# Gloves_Flex_PCB.net
KiCad netlist of a schematic drawn in EAGLE
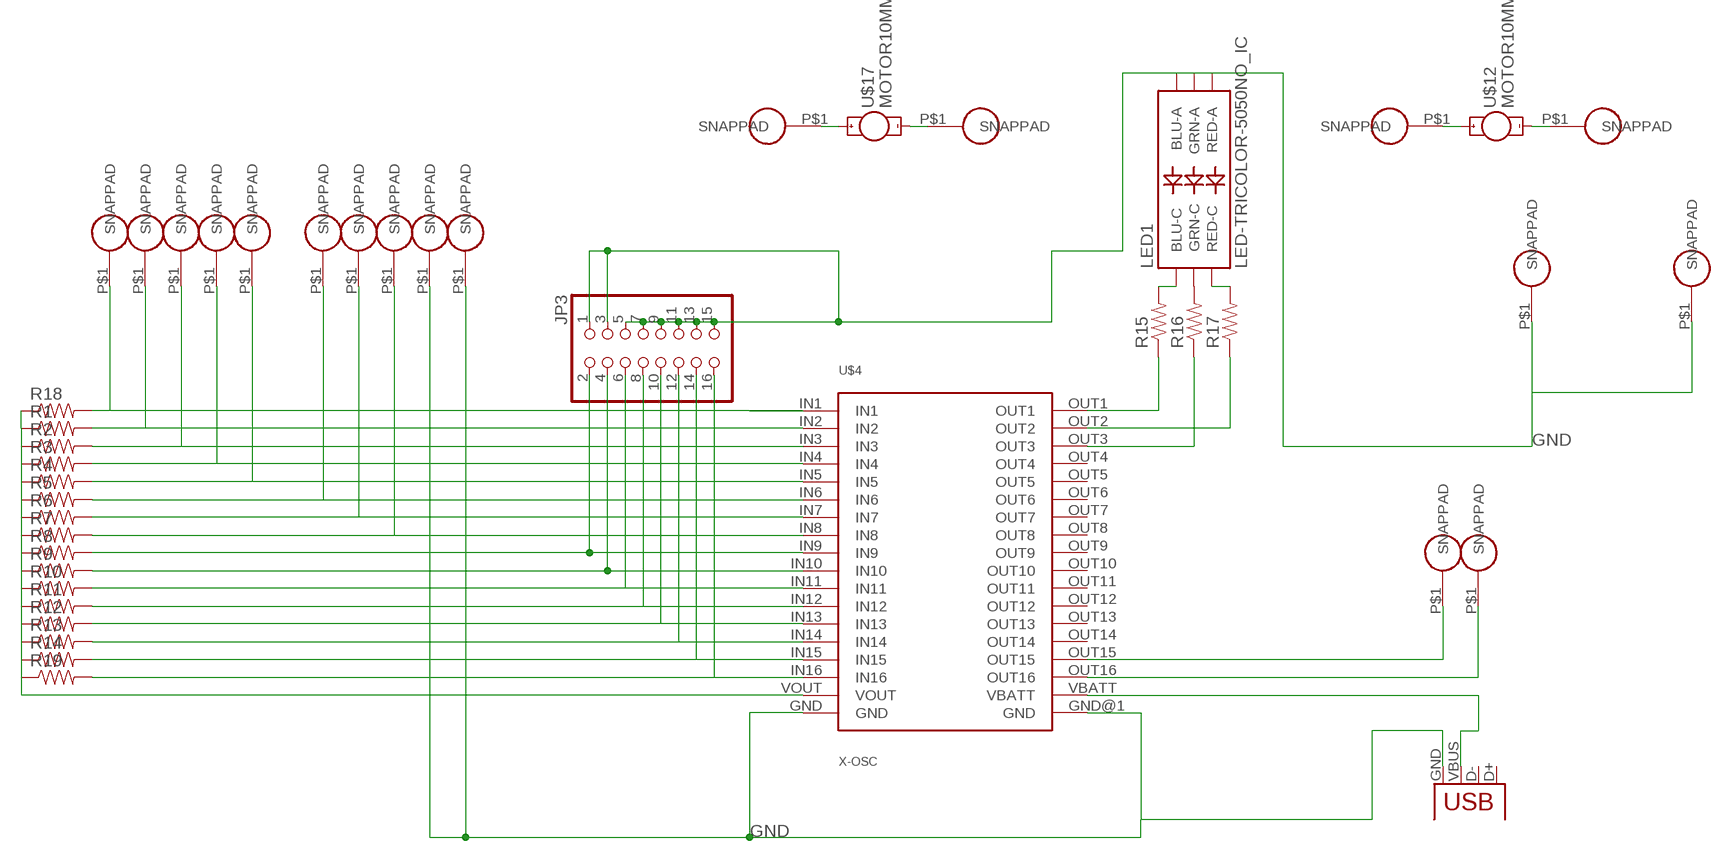
[diagram p0: schematic, sheet 1]

(export (version "E")
  (design (tool "Eeschema 10.0.6"))
  (components
    (comp (ref "JP3")
      (value "PINHD-2X8")
      (footprint "eagle-import:2X08")
      (libsource (lib "eagle-import") (part "PINHD-2X8"))
    )
    (comp (ref "LED1")
      (value "LED-TRICOLOR-5050NO_IC")
      (footprint "eagle-import:LED-TRICOLOR-5050")
      (libsource (lib "eagle-import") (part "LED-TRICOLOR-5050NO_IC"))
    )
    (comp (ref "R1")
      (value "RESISTOR0805-RES")
      (footprint "eagle-import:0805")
      (libsource (lib "eagle-import") (part "RESISTOR0805-RES"))
    )
    (comp (ref "R2")
      (value "RESISTOR0805-RES")
      (footprint "eagle-import:0805")
      (libsource (lib "eagle-import") (part "RESISTOR0805-RES"))
    )
    (comp (ref "R3")
      (value "RESISTOR0805-RES")
      (footprint "eagle-import:0805")
      (libsource (lib "eagle-import") (part "RESISTOR0805-RES"))
    )
    (comp (ref "R4")
      (value "RESISTOR0805-RES")
      (footprint "eagle-import:0805")
      (libsource (lib "eagle-import") (part "RESISTOR0805-RES"))
    )
    (comp (ref "R5")
      (value "RESISTOR0805-RES")
      (footprint "eagle-import:0805")
      (libsource (lib "eagle-import") (part "RESISTOR0805-RES"))
    )
    (comp (ref "R6")
      (value "RESISTOR0805-RES")
      (footprint "eagle-import:0805")
      (libsource (lib "eagle-import") (part "RESISTOR0805-RES"))
    )
    (comp (ref "R7")
      (value "RESISTOR0805-RES")
      (footprint "eagle-import:0805")
      (libsource (lib "eagle-import") (part "RESISTOR0805-RES"))
    )
    (comp (ref "R8")
      (value "RESISTOR0805-RES")
      (footprint "eagle-import:0805")
      (libsource (lib "eagle-import") (part "RESISTOR0805-RES"))
    )
    (comp (ref "R9")
      (value "RESISTOR0805-RES")
      (footprint "eagle-import:0805")
      (libsource (lib "eagle-import") (part "RESISTOR0805-RES"))
    )
    (comp (ref "R10")
      (value "RESISTOR0805-RES")
      (footprint "eagle-import:0805")
      (libsource (lib "eagle-import") (part "RESISTOR0805-RES"))
    )
    (comp (ref "R11")
      (value "RESISTOR0805-RES")
      (footprint "eagle-import:0805")
      (libsource (lib "eagle-import") (part "RESISTOR0805-RES"))
    )
    (comp (ref "R12")
      (value "RESISTOR0805-RES")
      (footprint "eagle-import:0805")
      (libsource (lib "eagle-import") (part "RESISTOR0805-RES"))
    )
    (comp (ref "R13")
      (value "RESISTOR0805-RES")
      (footprint "eagle-import:0805")
      (libsource (lib "eagle-import") (part "RESISTOR0805-RES"))
    )
    (comp (ref "R14")
      (value "RESISTOR0805-RES")
      (footprint "eagle-import:0805")
      (libsource (lib "eagle-import") (part "RESISTOR0805-RES"))
    )
    (comp (ref "R15")
      (value "RESISTOR0805-RES")
      (footprint "eagle-import:0805")
      (libsource (lib "eagle-import") (part "RESISTOR0805-RES"))
    )
    (comp (ref "R16")
      (value "RESISTOR0805-RES")
      (footprint "eagle-import:0805")
      (libsource (lib "eagle-import") (part "RESISTOR0805-RES"))
    )
    (comp (ref "R17")
      (value "RESISTOR0805-RES")
      (footprint "eagle-import:0805")
      (libsource (lib "eagle-import") (part "RESISTOR0805-RES"))
    )
    (comp (ref "R18")
      (value "RESISTOR0805-RES")
      (footprint "eagle-import:0805")
      (libsource (lib "eagle-import") (part "RESISTOR0805-RES"))
    )
    (comp (ref "R19")
      (value "RESISTOR0805-RES")
      (footprint "eagle-import:0805")
      (libsource (lib "eagle-import") (part "RESISTOR0805-RES"))
    )
    (comp (ref "U$1")
      (value "SNAP-PAD_7MM_ROUND")
      (footprint "eagle-import:SNAP-PAD_7MM_RD")
      (libsource (lib "eagle-import") (part "SNAP-PAD_7MM_ROUND"))
    )
    (comp (ref "U$2")
      (value "SNAP-PAD_7MM_ROUND")
      (footprint "eagle-import:SNAP-PAD_7MM_RD")
      (libsource (lib "eagle-import") (part "SNAP-PAD_7MM_ROUND"))
    )
    (comp (ref "U$3")
      (value "SNAP-PAD_7MM_ROUND")
      (footprint "eagle-import:SNAP-PAD_7MM_RD")
      (libsource (lib "eagle-import") (part "SNAP-PAD_7MM_ROUND"))
    )
    (comp (ref "U$4")
      (value "X-OSC")
      (footprint "eagle-import:X-OSC_SMD")
      (libsource (lib "eagle-import") (part "X-OSC"))
    )
    (comp (ref "U$6")
      (value "SNAP-PAD_7MM_ROUND")
      (footprint "eagle-import:SNAP-PAD_7MM_RD")
      (libsource (lib "eagle-import") (part "SNAP-PAD_7MM_ROUND"))
    )
    (comp (ref "U$7")
      (value "SNAP-PAD_7MM_ROUND")
      (footprint "eagle-import:SNAP-PAD_7MM_RD")
      (libsource (lib "eagle-import") (part "SNAP-PAD_7MM_ROUND"))
    )
    (comp (ref "U$8")
      (value "SNAP-PAD_7MM_ROUND")
      (footprint "eagle-import:SNAP-PAD_7MM_RD")
      (libsource (lib "eagle-import") (part "SNAP-PAD_7MM_ROUND"))
    )
    (comp (ref "U$9")
      (value "SNAP-PAD_7MM_ROUND")
      (footprint "eagle-import:SNAP-PAD_7MM_RD")
      (libsource (lib "eagle-import") (part "SNAP-PAD_7MM_ROUND"))
    )
    (comp (ref "U$10")
      (value "SNAP-PAD_7MM_ROUND")
      (footprint "eagle-import:SNAP-PAD_7MM_RD")
      (libsource (lib "eagle-import") (part "SNAP-PAD_7MM_ROUND"))
    )
    (comp (ref "U$11")
      (value "SNAP-PAD_7MM_ROUND")
      (footprint "eagle-import:SNAP-PAD_7MM_RD")
      (libsource (lib "eagle-import") (part "SNAP-PAD_7MM_ROUND"))
    )
    (comp (ref "U$12")
      (value "MOTOR10MM")
      (footprint "eagle-import:VIBE-MOTOR-10MM")
      (libsource (lib "eagle-import") (part "MOTOR10MM"))
    )
    (comp (ref "U$13")
      (value "SNAP-PAD_7MM_ROUND")
      (footprint "eagle-import:SNAP-PAD_7MM_RD")
      (libsource (lib "eagle-import") (part "SNAP-PAD_7MM_ROUND"))
    )
    (comp (ref "U$14")
      (value "SNAP-PAD_7MM_ROUND")
      (footprint "eagle-import:SNAP-PAD_7MM_RD")
      (libsource (lib "eagle-import") (part "SNAP-PAD_7MM_ROUND"))
    )
    (comp (ref "U$15")
      (value "SNAP-PAD_7MM_ROUND")
      (footprint "eagle-import:SNAP-PAD_7MM_RD")
      (libsource (lib "eagle-import") (part "SNAP-PAD_7MM_ROUND"))
    )
    (comp (ref "U$17")
      (value "MOTOR10MM")
      (footprint "eagle-import:VIBE-MOTOR-10MM")
      (libsource (lib "eagle-import") (part "MOTOR10MM"))
    )
    (comp (ref "U$18")
      (value "SNAP-PAD_7MM_ROUND")
      (footprint "eagle-import:SNAP-PAD_7MM_RD")
      (libsource (lib "eagle-import") (part "SNAP-PAD_7MM_ROUND"))
    )
    (comp (ref "U$19")
      (value "SNAP-PAD_7MM_ROUND")
      (footprint "eagle-import:SNAP-PAD_7MM_RD")
      (libsource (lib "eagle-import") (part "SNAP-PAD_7MM_ROUND"))
    )
    (comp (ref "U$20")
      (value "SNAP-PAD_7MM_ROUND")
      (footprint "eagle-import:SNAP-PAD_7MM_RD")
      (libsource (lib "eagle-import") (part "SNAP-PAD_7MM_ROUND"))
    )
    (comp (ref "U$21")
      (value "SNAP-PAD_7MM_ROUND")
      (footprint "eagle-import:SNAP-PAD_7MM_RD")
      (libsource (lib "eagle-import") (part "SNAP-PAD_7MM_ROUND"))
    )
    (comp (ref "U$22")
      (value "SNAP-PAD_7MM_ROUND")
      (footprint "eagle-import:SNAP-PAD_7MM_RD")
      (libsource (lib "eagle-import") (part "SNAP-PAD_7MM_ROUND"))
    )
    (comp (ref "U$23")
      (value "SNAP-PAD_7MM_ROUND")
      (footprint "eagle-import:SNAP-PAD_7MM_RD")
      (libsource (lib "eagle-import") (part "SNAP-PAD_7MM_ROUND"))
    )
    (comp (ref "X1")
      (value "USB-MICROB")
      (footprint "eagle-import:USB-MICROB")
      (libsource (lib "eagle-import") (part "USB-MICROB"))
    )
  )
  (nets
    (net (code "1") (name "/GND") (class "Default")
      (node (ref "JP3") (pin "1") (pinfunction "1_1") (pintype "passive"))
      (node (ref "JP3") (pin "11") (pinfunction "11_11") (pintype "passive"))
      (node (ref "JP3") (pin "13") (pinfunction "13_13") (pintype "passive"))
      (node (ref "JP3") (pin "15") (pinfunction "15_15") (pintype "passive"))
      (node (ref "JP3") (pin "3") (pinfunction "3_3") (pintype "passive"))
      (node (ref "JP3") (pin "5") (pinfunction "5_5") (pintype "passive"))
      (node (ref "JP3") (pin "7") (pinfunction "7_7") (pintype "passive"))
      (node (ref "JP3") (pin "9") (pinfunction "9_9") (pintype "passive"))
      (node (ref "LED1") (pin "1") (pinfunction "GRN-A_1") (pintype "bidirectional"))
      (node (ref "LED1") (pin "2") (pinfunction "RED-A_2") (pintype "bidirectional"))
      (node (ref "LED1") (pin "3") (pinfunction "BLU-A_3") (pintype "bidirectional"))
      (node (ref "U$10") (pin "P$1") (pinfunction "SNAPPAD_P$1") (pintype "bidirectional"))
      (node (ref "U$11") (pin "P$1") (pinfunction "SNAPPAD_P$1") (pintype "bidirectional"))
      (node (ref "U$15") (pin "P$1") (pinfunction "SNAPPAD_P$1") (pintype "bidirectional"))
      (node (ref "U$18") (pin "P$1") (pinfunction "SNAPPAD_P$1") (pintype "bidirectional"))
      (node (ref "U$4") (pin "GND") (pinfunction "GND_GND") (pintype "bidirectional"))
      (node (ref "U$4") (pin "GND@1") (pinfunction "GND_GND@1") (pintype "bidirectional"))
      (node (ref "X1") (pin "GND") (pinfunction "GND_GND") (pintype "bidirectional"))
    )
    (net (code "2") (name "Net-(JP3-Pad2)") (class "Default")
      (node (ref "JP3") (pin "2") (pinfunction "2_2") (pintype "passive"))
      (node (ref "R8") (pin "2") (pinfunction "2_2") (pintype "passive"))
      (node (ref "U$4") (pin "IN9") (pinfunction "IN9_IN9") (pintype "bidirectional"))
    )
    (net (code "3") (name "Net-(JP3-Pad4)") (class "Default")
      (node (ref "JP3") (pin "4") (pinfunction "4_4") (pintype "passive"))
      (node (ref "R9") (pin "2") (pinfunction "2_2") (pintype "passive"))
      (node (ref "U$4") (pin "IN10") (pinfunction "IN10_IN10") (pintype "bidirectional"))
    )
    (net (code "4") (name "Net-(JP3-Pad6)") (class "Default")
      (node (ref "JP3") (pin "6") (pinfunction "6_6") (pintype "passive"))
      (node (ref "R10") (pin "2") (pinfunction "2_2") (pintype "passive"))
      (node (ref "U$4") (pin "IN11") (pinfunction "IN11_IN11") (pintype "bidirectional"))
    )
    (net (code "5") (name "Net-(JP3-Pad8)") (class "Default")
      (node (ref "JP3") (pin "8") (pinfunction "8_8") (pintype "passive"))
      (node (ref "R11") (pin "2") (pinfunction "2_2") (pintype "passive"))
      (node (ref "U$4") (pin "IN12") (pinfunction "IN12_IN12") (pintype "bidirectional"))
    )
    (net (code "6") (name "Net-(JP3-Pad10)") (class "Default")
      (node (ref "JP3") (pin "10") (pinfunction "10_10") (pintype "passive"))
      (node (ref "R12") (pin "2") (pinfunction "2_2") (pintype "passive"))
      (node (ref "U$4") (pin "IN13") (pinfunction "IN13_IN13") (pintype "bidirectional"))
    )
    (net (code "7") (name "Net-(JP3-Pad12)") (class "Default")
      (node (ref "JP3") (pin "12") (pinfunction "12_12") (pintype "passive"))
      (node (ref "R13") (pin "2") (pinfunction "2_2") (pintype "passive"))
      (node (ref "U$4") (pin "IN14") (pinfunction "IN14_IN14") (pintype "bidirectional"))
    )
    (net (code "8") (name "Net-(JP3-Pad14)") (class "Default")
      (node (ref "JP3") (pin "14") (pinfunction "14_14") (pintype "passive"))
      (node (ref "R14") (pin "2") (pinfunction "2_2") (pintype "passive"))
      (node (ref "U$4") (pin "IN15") (pinfunction "IN15_IN15") (pintype "bidirectional"))
    )
    (net (code "9") (name "Net-(JP3-Pad16)") (class "Default")
      (node (ref "JP3") (pin "16") (pinfunction "16_16") (pintype "passive"))
      (node (ref "R19") (pin "2") (pinfunction "2_2") (pintype "passive"))
      (node (ref "U$4") (pin "IN16") (pinfunction "IN16_IN16") (pintype "bidirectional"))
    )
    (net (code "10") (name "Net-(LED1-BLU-C)") (class "Default")
      (node (ref "LED1") (pin "4") (pinfunction "BLU-C_4") (pintype "bidirectional"))
      (node (ref "R15") (pin "2") (pinfunction "2_2") (pintype "passive"))
    )
    (net (code "11") (name "Net-(LED1-GRN-C)") (class "Default")
      (node (ref "LED1") (pin "6") (pinfunction "GRN-C_6") (pintype "bidirectional"))
      (node (ref "R16") (pin "2") (pinfunction "2_2") (pintype "passive"))
    )
    (net (code "12") (name "Net-(LED1-RED-C)") (class "Default")
      (node (ref "LED1") (pin "5") (pinfunction "RED-C_5") (pintype "bidirectional"))
      (node (ref "R17") (pin "2") (pinfunction "2_2") (pintype "passive"))
    )
    (net (code "13") (name "Net-(R1-Pad1)") (class "Default")
      (node (ref "R1") (pin "1") (pinfunction "1_1") (pintype "passive"))
      (node (ref "R10") (pin "1") (pinfunction "1_1") (pintype "passive"))
      (node (ref "R11") (pin "1") (pinfunction "1_1") (pintype "passive"))
      (node (ref "R12") (pin "1") (pinfunction "1_1") (pintype "passive"))
      (node (ref "R13") (pin "1") (pinfunction "1_1") (pintype "passive"))
      (node (ref "R14") (pin "1") (pinfunction "1_1") (pintype "passive"))
      (node (ref "R18") (pin "1") (pinfunction "1_1") (pintype "passive"))
      (node (ref "R19") (pin "1") (pinfunction "1_1") (pintype "passive"))
      (node (ref "R2") (pin "1") (pinfunction "1_1") (pintype "passive"))
      (node (ref "R3") (pin "1") (pinfunction "1_1") (pintype "passive"))
      (node (ref "R4") (pin "1") (pinfunction "1_1") (pintype "passive"))
      (node (ref "R5") (pin "1") (pinfunction "1_1") (pintype "passive"))
      (node (ref "R6") (pin "1") (pinfunction "1_1") (pintype "passive"))
      (node (ref "R7") (pin "1") (pinfunction "1_1") (pintype "passive"))
      (node (ref "R8") (pin "1") (pinfunction "1_1") (pintype "passive"))
      (node (ref "R9") (pin "1") (pinfunction "1_1") (pintype "passive"))
      (node (ref "U$4") (pin "VOUT") (pinfunction "VOUT_VOUT") (pintype "bidirectional"))
    )
    (net (code "14") (name "Net-(R15-Pad1)") (class "Default")
      (node (ref "R15") (pin "1") (pinfunction "1_1") (pintype "passive"))
      (node (ref "U$4") (pin "OUT1") (pinfunction "OUT1_OUT1") (pintype "bidirectional"))
    )
    (net (code "15") (name "Net-(R16-Pad1)") (class "Default")
      (node (ref "R16") (pin "1") (pinfunction "1_1") (pintype "passive"))
      (node (ref "U$4") (pin "OUT3") (pinfunction "OUT3_OUT3") (pintype "bidirectional"))
    )
    (net (code "16") (name "Net-(R17-Pad1)") (class "Default")
      (node (ref "R17") (pin "1") (pinfunction "1_1") (pintype "passive"))
      (node (ref "U$4") (pin "OUT2") (pinfunction "OUT2_OUT2") (pintype "bidirectional"))
    )
    (net (code "17") (name "Net-(U$1-SNAPPAD)") (class "Default")
      (node (ref "R1") (pin "2") (pinfunction "2_2") (pintype "passive"))
      (node (ref "U$1") (pin "P$1") (pinfunction "SNAPPAD_P$1") (pintype "bidirectional"))
      (node (ref "U$4") (pin "IN2") (pinfunction "IN2_IN2") (pintype "bidirectional"))
    )
    (net (code "18") (name "Net-(U$2-SNAPPAD)") (class "Default")
      (node (ref "R2") (pin "2") (pinfunction "2_2") (pintype "passive"))
      (node (ref "U$2") (pin "P$1") (pinfunction "SNAPPAD_P$1") (pintype "bidirectional"))
      (node (ref "U$4") (pin "IN3") (pinfunction "IN3_IN3") (pintype "bidirectional"))
    )
    (net (code "19") (name "Net-(U$3-SNAPPAD)") (class "Default")
      (node (ref "R3") (pin "2") (pinfunction "2_2") (pintype "passive"))
      (node (ref "U$3") (pin "P$1") (pinfunction "SNAPPAD_P$1") (pintype "bidirectional"))
      (node (ref "U$4") (pin "IN4") (pinfunction "IN4_IN4") (pintype "bidirectional"))
    )
    (net (code "20") (name "Net-(U$4-PadVBATT)") (class "Default")
      (node (ref "U$4") (pin "VBATT") (pinfunction "VBATT_VBATT") (pintype "bidirectional"))
      (node (ref "X1") (pin "VBUS") (pinfunction "VBUS_VBUS") (pintype "bidirectional"))
    )
    (net (code "21") (name "Net-(U$6-SNAPPAD)") (class "Default")
      (node (ref "R4") (pin "2") (pinfunction "2_2") (pintype "passive"))
      (node (ref "U$4") (pin "IN5") (pinfunction "IN5_IN5") (pintype "bidirectional"))
      (node (ref "U$6") (pin "P$1") (pinfunction "SNAPPAD_P$1") (pintype "bidirectional"))
    )
    (net (code "22") (name "Net-(U$7-SNAPPAD)") (class "Default")
      (node (ref "R5") (pin "2") (pinfunction "2_2") (pintype "passive"))
      (node (ref "U$4") (pin "IN6") (pinfunction "IN6_IN6") (pintype "bidirectional"))
      (node (ref "U$7") (pin "P$1") (pinfunction "SNAPPAD_P$1") (pintype "bidirectional"))
    )
    (net (code "23") (name "Net-(U$8-SNAPPAD)") (class "Default")
      (node (ref "R6") (pin "2") (pinfunction "2_2") (pintype "passive"))
      (node (ref "U$4") (pin "IN7") (pinfunction "IN7_IN7") (pintype "bidirectional"))
      (node (ref "U$8") (pin "P$1") (pinfunction "SNAPPAD_P$1") (pintype "bidirectional"))
    )
    (net (code "24") (name "Net-(U$9-SNAPPAD)") (class "Default")
      (node (ref "R7") (pin "2") (pinfunction "2_2") (pintype "passive"))
      (node (ref "U$4") (pin "IN8") (pinfunction "IN8_IN8") (pintype "bidirectional"))
      (node (ref "U$9") (pin "P$1") (pinfunction "SNAPPAD_P$1") (pintype "bidirectional"))
    )
    (net (code "25") (name "Net-(U$13-SNAPPAD)") (class "Default")
      (node (ref "U$13") (pin "P$1") (pinfunction "SNAPPAD_P$1") (pintype "bidirectional"))
      (node (ref "U$4") (pin "OUT15") (pinfunction "OUT15_OUT15") (pintype "bidirectional"))
    )
    (net (code "26") (name "Net-(U$14-SNAPPAD)") (class "Default")
      (node (ref "U$14") (pin "P$1") (pinfunction "SNAPPAD_P$1") (pintype "bidirectional"))
      (node (ref "U$4") (pin "OUT16") (pinfunction "OUT16_OUT16") (pintype "bidirectional"))
    )
    (net (code "27") (name "Net-(U$19-SNAPPAD)") (class "Default")
      (node (ref "U$17") (pin "+") (pinfunction "+_+") (pintype "bidirectional"))
      (node (ref "U$19") (pin "P$1") (pinfunction "SNAPPAD_P$1") (pintype "bidirectional"))
    )
    (net (code "28") (name "Net-(U$20-SNAPPAD)") (class "Default")
      (node (ref "U$17") (pin "-") (pinfunction "-_-") (pintype "bidirectional"))
      (node (ref "U$20") (pin "P$1") (pinfunction "SNAPPAD_P$1") (pintype "bidirectional"))
    )
    (net (code "29") (name "Net-(U$21-SNAPPAD)") (class "Default")
      (node (ref "R18") (pin "2") (pinfunction "2_2") (pintype "passive"))
      (node (ref "U$21") (pin "P$1") (pinfunction "SNAPPAD_P$1") (pintype "bidirectional"))
      (node (ref "U$4") (pin "IN1") (pinfunction "IN1_IN1") (pintype "bidirectional"))
    )
    (net (code "30") (name "Net-(U$22-SNAPPAD)") (class "Default")
      (node (ref "U$12") (pin "+") (pinfunction "+_+") (pintype "bidirectional"))
      (node (ref "U$22") (pin "P$1") (pinfunction "SNAPPAD_P$1") (pintype "bidirectional"))
    )
    (net (code "31") (name "Net-(U$23-SNAPPAD)") (class "Default")
      (node (ref "U$12") (pin "-") (pinfunction "-_-") (pintype "bidirectional"))
      (node (ref "U$23") (pin "P$1") (pinfunction "SNAPPAD_P$1") (pintype "bidirectional"))
    )
    (net (code "32") (name "unconnected-(U$4-PadOUT4)") (class "Default")
      (node (ref "U$4") (pin "OUT4") (pinfunction "OUT4_OUT4") (pintype "bidirectional"))
    )
    (net (code "33") (name "unconnected-(U$4-PadOUT5)") (class "Default")
      (node (ref "U$4") (pin "OUT5") (pinfunction "OUT5_OUT5") (pintype "bidirectional"))
    )
    (net (code "34") (name "unconnected-(U$4-PadOUT6)") (class "Default")
      (node (ref "U$4") (pin "OUT6") (pinfunction "OUT6_OUT6") (pintype "bidirectional"))
    )
    (net (code "35") (name "unconnected-(U$4-PadOUT7)") (class "Default")
      (node (ref "U$4") (pin "OUT7") (pinfunction "OUT7_OUT7") (pintype "bidirectional"))
    )
    (net (code "36") (name "unconnected-(U$4-PadOUT8)") (class "Default")
      (node (ref "U$4") (pin "OUT8") (pinfunction "OUT8_OUT8") (pintype "bidirectional"))
    )
    (net (code "37") (name "unconnected-(U$4-PadOUT9)") (class "Default")
      (node (ref "U$4") (pin "OUT9") (pinfunction "OUT9_OUT9") (pintype "bidirectional"))
    )
    (net (code "38") (name "unconnected-(U$4-PadOUT10)") (class "Default")
      (node (ref "U$4") (pin "OUT10") (pinfunction "OUT10_OUT10") (pintype "bidirectional"))
    )
    (net (code "39") (name "unconnected-(U$4-PadOUT11)") (class "Default")
      (node (ref "U$4") (pin "OUT11") (pinfunction "OUT11_OUT11") (pintype "bidirectional"))
    )
    (net (code "40") (name "unconnected-(U$4-PadOUT12)") (class "Default")
      (node (ref "U$4") (pin "OUT12") (pinfunction "OUT12_OUT12") (pintype "bidirectional"))
    )
    (net (code "41") (name "unconnected-(U$4-PadOUT13)") (class "Default")
      (node (ref "U$4") (pin "OUT13") (pinfunction "OUT13_OUT13") (pintype "bidirectional"))
    )
    (net (code "42") (name "unconnected-(U$4-PadOUT14)") (class "Default")
      (node (ref "U$4") (pin "OUT14") (pinfunction "OUT14_OUT14") (pintype "bidirectional"))
    )
    (net (code "43") (name "unconnected-(X1-PadD+)") (class "Default")
      (node (ref "X1") (pin "D+") (pinfunction "D+_D+") (pintype "bidirectional"))
    )
    (net (code "44") (name "unconnected-(X1-PadD-)") (class "Default")
      (node (ref "X1") (pin "D-") (pinfunction "D-_D-") (pintype "bidirectional"))
    )
  )
)
